# Oscillator_50MHz.net
KiCad netlist of a schematic drawn in Altium Designer
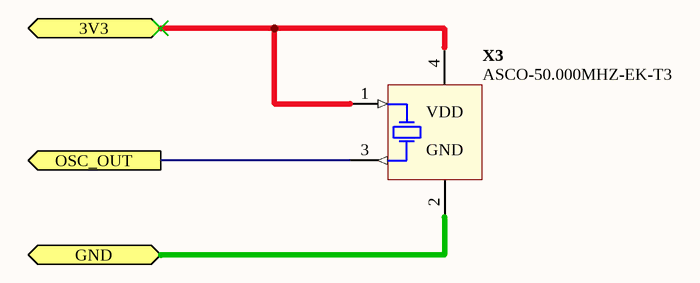
[diagram p0: Oscillator_50MHz.SchDoc]

(export (version "E")
  (design (tool "Eeschema 10.0.6"))
  (components
    (comp (ref "X3")
      (value "ASCO-50.000MHZ-EK-T3")
      (footprint "ABRA-ASCO-50.000MHZ-EK-T3-4_V")
      (description "Crystal Clock Oscillator, 50 MHz, -20 to 70 degC, 1.6 x 1.2 x 0.7 mm SMD")
      (fields (field (name "MANUFACTURER") "Abracon"))
      (libsource (lib "Altium Content Vault") (part "ABRA-ASCO-50_000MHZ-EK-T3-4"))
    )
  )
  (nets
    (net (code "1") (name "/3V3") (class "Default")
      (node (ref "X3") (pin "1") (pinfunction "STAND-BY_1") (pintype "input"))
      (node (ref "X3") (pin "4") (pinfunction "VDD_4") (pintype "power_in"))
    )
    (net (code "2") (name "/GND") (class "Default")
      (node (ref "X3") (pin "2") (pinfunction "GND_2") (pintype "power_in"))
    )
    (net (code "3") (name "/OSC_OUT") (class "Default")
      (node (ref "X3") (pin "3") (pinfunction "OUTPUT_3") (pintype "output"))
    )
  )
)
